# NESRGB-IGR.net
KiCad netlist of a schematic drawn in EAGLE
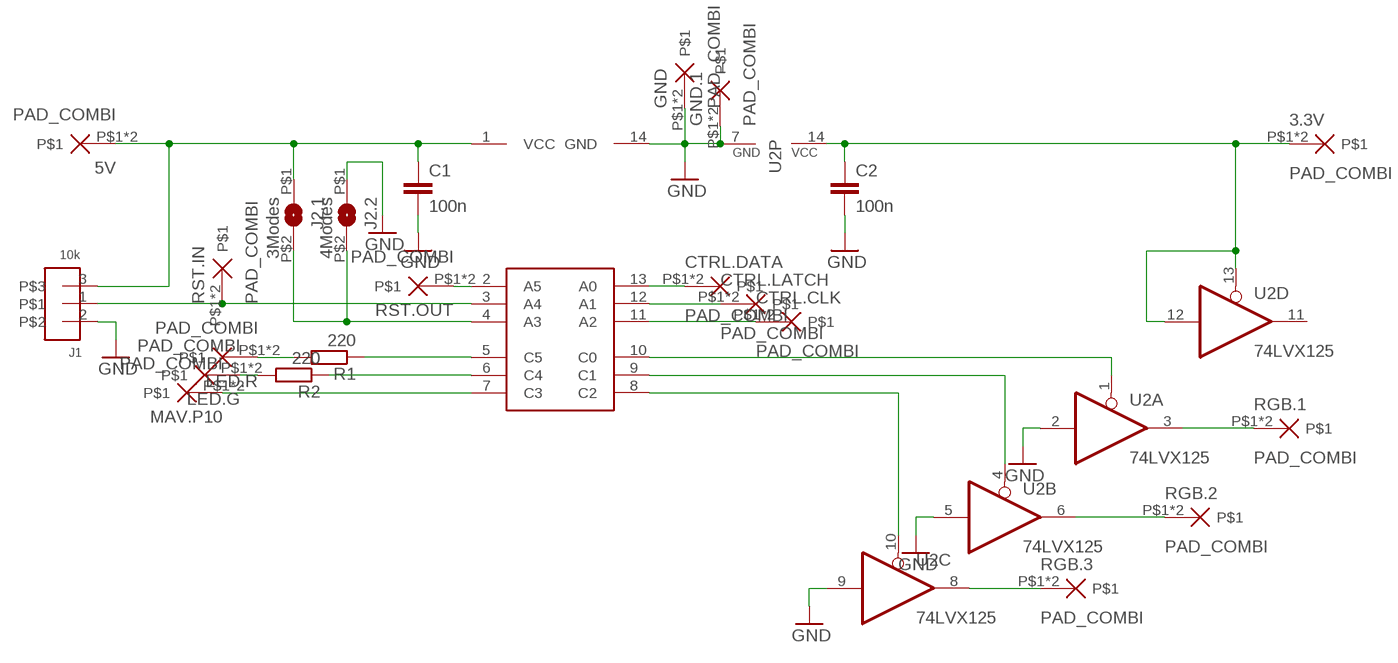
[diagram p0: schematic, sheet 1]

(export (version "E")
  (design (tool "Eeschema 10.0.6"))
  (components
    (comp (ref "3.3V")
      (value "PAD_COMBI")
      (footprint "eagle-import:PAD_COMBI")
      (libsource (lib "eagle-import") (part "PAD_COMBI"))
    )
    (comp (ref "5V")
      (value "PAD_COMBI")
      (footprint "eagle-import:PAD_COMBI")
      (libsource (lib "eagle-import") (part "PAD_COMBI"))
    )
    (comp (ref "C1")
      (value "100n")
      (footprint "eagle-import:Z0805")
      (libsource (lib "eagle-import") (part "C0805"))
    )
    (comp (ref "C2")
      (value "100n")
      (footprint "eagle-import:Z0805")
      (libsource (lib "eagle-import") (part "C0805"))
    )
    (comp (ref "CTRL.CLK")
      (value "PAD_COMBI")
      (footprint "eagle-import:PAD_COMBI")
      (libsource (lib "eagle-import") (part "PAD_COMBI"))
    )
    (comp (ref "CTRL.DATA")
      (value "PAD_COMBI")
      (footprint "eagle-import:PAD_COMBI")
      (libsource (lib "eagle-import") (part "PAD_COMBI"))
    )
    (comp (ref "CTRL.LATCH")
      (value "PAD_COMBI")
      (footprint "eagle-import:PAD_COMBI")
      (libsource (lib "eagle-import") (part "PAD_COMBI"))
    )
    (comp (ref "GND")
      (value "PAD_COMBI")
      (footprint "eagle-import:PAD_COMBI")
      (libsource (lib "eagle-import") (part "PAD_COMBI"))
    )
    (comp (ref "GND.1")
      (value "PAD_COMBI")
      (footprint "eagle-import:PAD_COMBI")
      (libsource (lib "eagle-import") (part "PAD_COMBI"))
    )
    (comp (ref "J1")
      (value "10k")
      (footprint "eagle-import:Z0805-JUMPER")
      (libsource (lib "eagle-import") (part "Z0805-JUMPER"))
    )
    (comp (ref "J2.1")
      (value "3Modes")
      (footprint "eagle-import:MYJUMP")
      (libsource (lib "eagle-import") (part "MY_JUMPER"))
    )
    (comp (ref "J2.2")
      (value "4Modes")
      (footprint "eagle-import:MYJUMP")
      (libsource (lib "eagle-import") (part "MY_JUMPER"))
    )
    (comp (ref "LED.G")
      (value "PAD_COMBI")
      (footprint "eagle-import:PAD_COMBI")
      (libsource (lib "eagle-import") (part "PAD_COMBI"))
    )
    (comp (ref "LED.R")
      (value "PAD_COMBI")
      (footprint "eagle-import:PAD_COMBI")
      (libsource (lib "eagle-import") (part "PAD_COMBI"))
    )
    (comp (ref "MAV.P10")
      (value "PAD_COMBI")
      (footprint "eagle-import:PAD_COMBI")
      (libsource (lib "eagle-import") (part "PAD_COMBI"))
    )
    (comp (ref "R1")
      (value "220")
      (footprint "eagle-import:Z0805")
      (libsource (lib "eagle-import") (part "R0805"))
    )
    (comp (ref "R2")
      (value "220")
      (footprint "eagle-import:Z0805")
      (libsource (lib "eagle-import") (part "R0805"))
    )
    (comp (ref "RGB.1")
      (value "PAD_COMBI")
      (footprint "eagle-import:PAD_COMBI")
      (libsource (lib "eagle-import") (part "PAD_COMBI"))
    )
    (comp (ref "RGB.2")
      (value "PAD_COMBI")
      (footprint "eagle-import:PAD_COMBI")
      (libsource (lib "eagle-import") (part "PAD_COMBI"))
    )
    (comp (ref "RGB.3")
      (value "PAD_COMBI")
      (footprint "eagle-import:PAD_COMBI")
      (libsource (lib "eagle-import") (part "PAD_COMBI"))
    )
    (comp (ref "RST.IN")
      (value "PAD_COMBI")
      (footprint "eagle-import:PAD_COMBI")
      (libsource (lib "eagle-import") (part "PAD_COMBI"))
    )
    (comp (ref "RST.OUT")
      (value "PAD_COMBI")
      (footprint "eagle-import:PAD_COMBI")
      (libsource (lib "eagle-import") (part "PAD_COMBI"))
    )
    (comp (ref "U1")
      (value "PIC16F684")
      (footprint "eagle-import:PIC16F630")
      (libsource (lib "eagle-import") (part "PIC16F630_SIMPLE"))
    )
    (comp (ref "U2")
      (value "74LVX125")
      (footprint "eagle-import:SO14")
      (libsource (lib "eagle-import") (part "74125DHC"))
    )
  )
  (nets
    (net (code "1") (name "GND") (class "Default")
      (node (ref "C1") (pin "2") (pinfunction "2_2") (pintype "passive"))
      (node (ref "C2") (pin "2") (pinfunction "2_2") (pintype "passive"))
      (node (ref "GND") (pin "P$1") (pinfunction "P$1_P$1") (pintype "bidirectional"))
      (node (ref "GND") (pin "P$2") (pinfunction "P$1_P$2") (pintype "bidirectional"))
      (node (ref "GND.1") (pin "P$1") (pinfunction "P$1_P$1") (pintype "bidirectional"))
      (node (ref "GND.1") (pin "P$2") (pinfunction "P$1_P$2") (pintype "bidirectional"))
      (node (ref "J1") (pin "2") (pinfunction "P$2_2") (pintype "bidirectional"))
      (node (ref "J2.2") (pin "P$1") (pinfunction "1_P$1") (pintype "passive"))
      (node (ref "U1") (pin "14") (pinfunction "GND_14") (pintype "bidirectional"))
      (node (ref "U2") (pin "2") (pinfunction "I_2") (pintype "input"))
      (node (ref "U2") (pin "5") (pinfunction "I_5") (pintype "input"))
      (node (ref "U2") (pin "7") (pinfunction "GND_7") (pintype "power_in"))
      (node (ref "U2") (pin "9") (pinfunction "I_9") (pintype "input"))
    )
    (net (code "2") (name "Net-(J1-P$1)") (class "Default")
      (node (ref "J1") (pin "1") (pinfunction "P$1_1") (pintype "bidirectional"))
      (node (ref "RST.IN") (pin "P$1") (pinfunction "P$1_P$1") (pintype "bidirectional"))
      (node (ref "RST.IN") (pin "P$2") (pinfunction "P$1_P$2") (pintype "bidirectional"))
      (node (ref "U1") (pin "3") (pinfunction "A4_3") (pintype "bidirectional"))
    )
    (net (code "3") (name "Net-(J1-P$3)") (class "Default")
      (node (ref "5V") (pin "P$1") (pinfunction "P$1_P$1") (pintype "bidirectional"))
      (node (ref "5V") (pin "P$2") (pinfunction "P$1_P$2") (pintype "bidirectional"))
      (node (ref "C1") (pin "1") (pinfunction "1_1") (pintype "passive"))
      (node (ref "J1") (pin "3") (pinfunction "P$3_3") (pintype "bidirectional"))
      (node (ref "J2.1") (pin "P$1") (pinfunction "1_P$1") (pintype "passive"))
      (node (ref "U1") (pin "1") (pinfunction "VCC_1") (pintype "bidirectional"))
    )
    (net (code "4") (name "Net-(J2.1-2)") (class "Default")
      (node (ref "J2.1") (pin "P$2") (pinfunction "2_P$2") (pintype "passive"))
      (node (ref "J2.2") (pin "P$2") (pinfunction "2_P$2") (pintype "passive"))
      (node (ref "U1") (pin "4") (pinfunction "A3_4") (pintype "bidirectional"))
    )
    (net (code "5") (name "Net-(LED.G-P$1-PadP$2)") (class "Default")
      (node (ref "LED.G") (pin "P$1") (pinfunction "P$1_P$1") (pintype "bidirectional"))
      (node (ref "LED.G") (pin "P$2") (pinfunction "P$1_P$2") (pintype "bidirectional"))
      (node (ref "R2") (pin "2") (pinfunction "2_2") (pintype "passive"))
    )
    (net (code "6") (name "Net-(LED.R-P$1-PadP$2)") (class "Default")
      (node (ref "LED.R") (pin "P$1") (pinfunction "P$1_P$1") (pintype "bidirectional"))
      (node (ref "LED.R") (pin "P$2") (pinfunction "P$1_P$2") (pintype "bidirectional"))
      (node (ref "R1") (pin "2") (pinfunction "2_2") (pintype "passive"))
    )
    (net (code "7") (name "Net-(U1A-A0)") (class "Default")
      (node (ref "CTRL.DATA") (pin "P$1") (pinfunction "P$1_P$1") (pintype "bidirectional"))
      (node (ref "CTRL.DATA") (pin "P$2") (pinfunction "P$1_P$2") (pintype "bidirectional"))
      (node (ref "U1") (pin "13") (pinfunction "A0_13") (pintype "bidirectional"))
    )
    (net (code "8") (name "Net-(U1A-A1)") (class "Default")
      (node (ref "CTRL.LATCH") (pin "P$1") (pinfunction "P$1_P$1") (pintype "bidirectional"))
      (node (ref "CTRL.LATCH") (pin "P$2") (pinfunction "P$1_P$2") (pintype "bidirectional"))
      (node (ref "U1") (pin "12") (pinfunction "A1_12") (pintype "bidirectional"))
    )
    (net (code "9") (name "Net-(U1A-A2)") (class "Default")
      (node (ref "CTRL.CLK") (pin "P$1") (pinfunction "P$1_P$1") (pintype "bidirectional"))
      (node (ref "CTRL.CLK") (pin "P$2") (pinfunction "P$1_P$2") (pintype "bidirectional"))
      (node (ref "U1") (pin "11") (pinfunction "A2_11") (pintype "bidirectional"))
    )
    (net (code "10") (name "Net-(U1A-A5)") (class "Default")
      (node (ref "RST.OUT") (pin "P$1") (pinfunction "P$1_P$1") (pintype "bidirectional"))
      (node (ref "RST.OUT") (pin "P$2") (pinfunction "P$1_P$2") (pintype "bidirectional"))
      (node (ref "U1") (pin "2") (pinfunction "A5_2") (pintype "bidirectional"))
    )
    (net (code "11") (name "Net-(U1A-C0)") (class "Default")
      (node (ref "U1") (pin "10") (pinfunction "C0_10") (pintype "bidirectional"))
      (node (ref "U2") (pin "1") (pinfunction "OE_1") (pintype "input"))
    )
    (net (code "12") (name "Net-(U1A-C1)") (class "Default")
      (node (ref "U1") (pin "9") (pinfunction "C1_9") (pintype "bidirectional"))
      (node (ref "U2") (pin "4") (pinfunction "OE_4") (pintype "input"))
    )
    (net (code "13") (name "Net-(U1A-C2)") (class "Default")
      (node (ref "U1") (pin "8") (pinfunction "C2_8") (pintype "bidirectional"))
      (node (ref "U2") (pin "10") (pinfunction "OE_10") (pintype "input"))
    )
    (net (code "14") (name "Net-(U1A-C3)") (class "Default")
      (node (ref "MAV.P10") (pin "P$1") (pinfunction "P$1_P$1") (pintype "bidirectional"))
      (node (ref "MAV.P10") (pin "P$2") (pinfunction "P$1_P$2") (pintype "bidirectional"))
      (node (ref "U1") (pin "7") (pinfunction "C3_7") (pintype "bidirectional"))
    )
    (net (code "15") (name "Net-(U1A-C4)") (class "Default")
      (node (ref "R2") (pin "1") (pinfunction "1_1") (pintype "passive"))
      (node (ref "U1") (pin "6") (pinfunction "C4_6") (pintype "bidirectional"))
    )
    (net (code "16") (name "Net-(U1A-C5)") (class "Default")
      (node (ref "R1") (pin "1") (pinfunction "1_1") (pintype "passive"))
      (node (ref "U1") (pin "5") (pinfunction "C5_5") (pintype "bidirectional"))
    )
    (net (code "17") (name "Net-(U2A-O)") (class "Default")
      (node (ref "RGB.1") (pin "P$1") (pinfunction "P$1_P$1") (pintype "bidirectional"))
      (node (ref "RGB.1") (pin "P$2") (pinfunction "P$1_P$2") (pintype "bidirectional"))
      (node (ref "U2") (pin "3") (pinfunction "O_3") (pintype "tri_state"))
    )
    (net (code "18") (name "Net-(U2B-O)") (class "Default")
      (node (ref "RGB.2") (pin "P$1") (pinfunction "P$1_P$1") (pintype "bidirectional"))
      (node (ref "RGB.2") (pin "P$2") (pinfunction "P$1_P$2") (pintype "bidirectional"))
      (node (ref "U2") (pin "6") (pinfunction "O_6") (pintype "tri_state"))
    )
    (net (code "19") (name "Net-(U2C-O)") (class "Default")
      (node (ref "RGB.3") (pin "P$1") (pinfunction "P$1_P$1") (pintype "bidirectional"))
      (node (ref "RGB.3") (pin "P$2") (pinfunction "P$1_P$2") (pintype "bidirectional"))
      (node (ref "U2") (pin "8") (pinfunction "O_8") (pintype "tri_state"))
    )
    (net (code "20") (name "Net-(U2D-I)") (class "Default")
      (node (ref "3.3V") (pin "P$1") (pinfunction "P$1_P$1") (pintype "bidirectional"))
      (node (ref "3.3V") (pin "P$2") (pinfunction "P$1_P$2") (pintype "bidirectional"))
      (node (ref "C2") (pin "1") (pinfunction "1_1") (pintype "passive"))
      (node (ref "U2") (pin "12") (pinfunction "I_12") (pintype "input"))
      (node (ref "U2") (pin "13") (pinfunction "OE_13") (pintype "input"))
      (node (ref "U2") (pin "14") (pinfunction "VCC_14") (pintype "power_in"))
    )
    (net (code "21") (name "unconnected-(U2D-O-Pad11)") (class "Default")
      (node (ref "U2") (pin "11") (pinfunction "O_11") (pintype "tri_state"))
    )
  )
)
